# Interface_Protection.net
KiCad netlist of a schematic drawn in Altium Designer
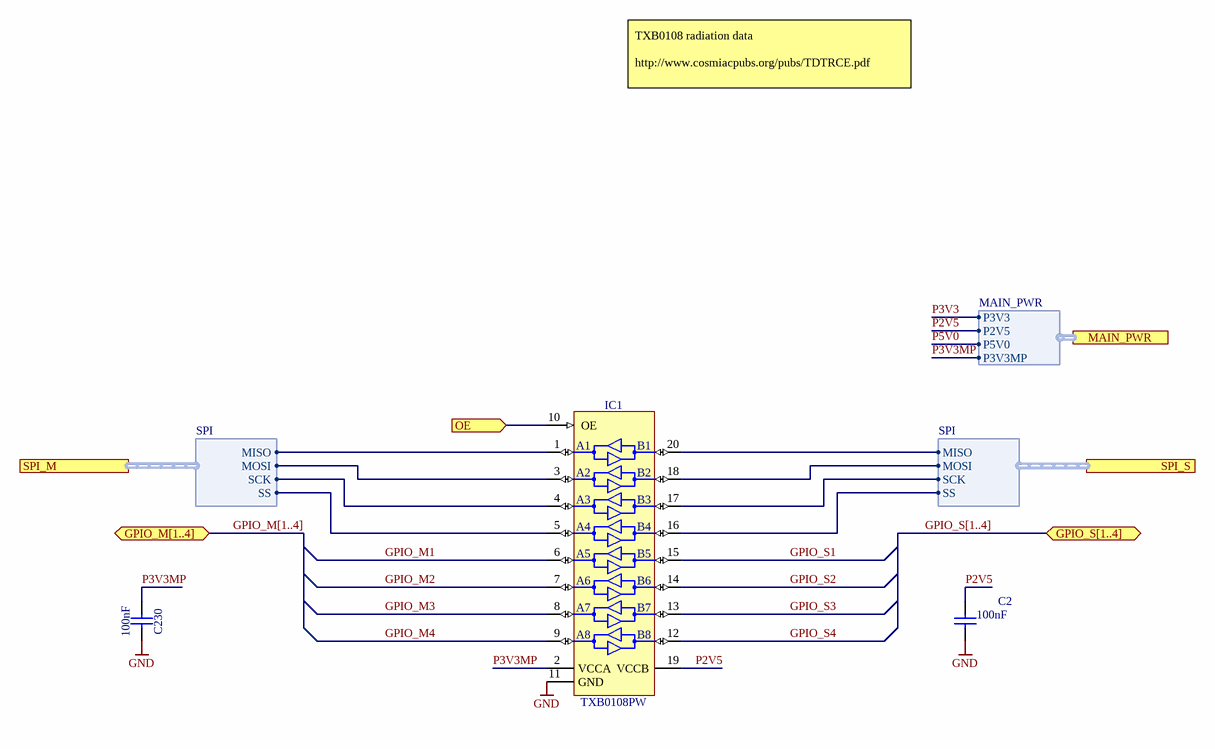
[diagram p0: Interface_Protection.SchDoc]

(export (version "E")
  (design (tool "Eeschema 10.0.6"))
  (components
    (comp (ref "C2")
      (value "100nF")
      (footprint "CAPC1005X55N")
      (description "Non-polarised capacitor")
      (fields
        (field (name "PART NUMBER") "CC0402_100NF_25V_10%_X7R_YUDEN_TMK105B7104KVHF")
        (field (name "VOLTAGE") "25V")
        (field (name "AUTHOR") "CERN DEM JLC")
      )
      (libsource (lib "Capacitors") (part "Capacitor - non polarized"))
    )
    (comp (ref "C230")
      (value "100nF")
      (footprint "CAPC1005X55N")
      (description "Non-polarised capacitor")
      (fields
        (field (name "PART NUMBER") "CC0402_100NF_25V_10%_X7R_YUDEN_TMK105B7104KVHF")
        (field (name "VOLTAGE") "25V")
        (field (name "AUTHOR") "CERN DEM JLC")
      )
      (libsource (lib "Capacitors") (part "Capacitor - non polarized"))
    )
    (comp (ref "IC1")
      (value "TXB0108PW")
      (footprint "SOP65P640X120-20N")
      (fields (field (name "MANUFACTURER") "TEXAS INSTRUMENTS") (field (name "AUTHOR") "CERN DEM MR"))
      (libsource (lib "ICs And Semiconductors") (part "TXB0108PW"))
    )
  )
  (nets
    (net (code "3") (name "/GPIO_M1") (class "Default")
      (node (ref "IC1") (pin "6") (pinfunction "A5_6") (pintype "bidirectional"))
    )
    (net (code "4") (name "/GPIO_M2") (class "Default")
      (node (ref "IC1") (pin "7") (pinfunction "A6_7") (pintype "bidirectional"))
    )
    (net (code "5") (name "/GPIO_M3") (class "Default")
      (node (ref "IC1") (pin "8") (pinfunction "A7_8") (pintype "bidirectional"))
    )
    (net (code "6") (name "/GPIO_M4") (class "Default")
      (node (ref "IC1") (pin "9") (pinfunction "A8_9") (pintype "bidirectional"))
    )
    (net (code "8") (name "/GPIO_S1") (class "Default")
      (node (ref "IC1") (pin "15") (pinfunction "B5_15") (pintype "bidirectional"))
    )
    (net (code "9") (name "/GPIO_S2") (class "Default")
      (node (ref "IC1") (pin "14") (pinfunction "B6_14") (pintype "bidirectional"))
    )
    (net (code "10") (name "/GPIO_S3") (class "Default")
      (node (ref "IC1") (pin "13") (pinfunction "B7_13") (pintype "bidirectional"))
    )
    (net (code "11") (name "/GPIO_S4") (class "Default")
      (node (ref "IC1") (pin "12") (pinfunction "B8_12") (pintype "bidirectional"))
    )
    (net (code "13") (name "/OE") (class "Default")
      (node (ref "IC1") (pin "10") (pinfunction "OE_10") (pintype "input"))
    )
    (net (code "14") (name "/P2V5") (class "Default")
      (node (ref "C2") (pin "1") (pinfunction "1_1") (pintype "passive"))
      (node (ref "IC1") (pin "19") (pinfunction "Vccb_19") (pintype "power_in"))
    )
    (net (code "16") (name "/P3V3MP") (class "Default")
      (node (ref "C230") (pin "1") (pinfunction "1_1") (pintype "passive"))
      (node (ref "IC1") (pin "2") (pinfunction "Vcca_2") (pintype "power_in"))
    )
    (net (code "20") (name "GND") (class "Default")
      (node (ref "C2") (pin "2") (pinfunction "2_2") (pintype "passive"))
      (node (ref "C230") (pin "2") (pinfunction "2_2") (pintype "passive"))
      (node (ref "IC1") (pin "11") (pinfunction "GND_11") (pintype "power_in"))
    )
    (net (code "21") (name "unconnected-(IC1-A1-Pad1)") (class "Default")
      (node (ref "IC1") (pin "1") (pinfunction "A1_1") (pintype "bidirectional"))
    )
    (net (code "22") (name "unconnected-(IC1-A2-Pad3)") (class "Default")
      (node (ref "IC1") (pin "3") (pinfunction "A2_3") (pintype "bidirectional"))
    )
    (net (code "23") (name "unconnected-(IC1-A3-Pad4)") (class "Default")
      (node (ref "IC1") (pin "4") (pinfunction "A3_4") (pintype "bidirectional"))
    )
    (net (code "24") (name "unconnected-(IC1-A4-Pad5)") (class "Default")
      (node (ref "IC1") (pin "5") (pinfunction "A4_5") (pintype "bidirectional"))
    )
    (net (code "25") (name "unconnected-(IC1-B1-Pad20)") (class "Default")
      (node (ref "IC1") (pin "20") (pinfunction "B1_20") (pintype "bidirectional"))
    )
    (net (code "26") (name "unconnected-(IC1-B2-Pad18)") (class "Default")
      (node (ref "IC1") (pin "18") (pinfunction "B2_18") (pintype "bidirectional"))
    )
    (net (code "27") (name "unconnected-(IC1-B3-Pad17)") (class "Default")
      (node (ref "IC1") (pin "17") (pinfunction "B3_17") (pintype "bidirectional"))
    )
    (net (code "28") (name "unconnected-(IC1-B4-Pad16)") (class "Default")
      (node (ref "IC1") (pin "16") (pinfunction "B4_16") (pintype "bidirectional"))
    )
  )
)
